# Modulo_Ignicao_Enertron_proto.net
KiCad netlist of a schematic drawn in EAGLE
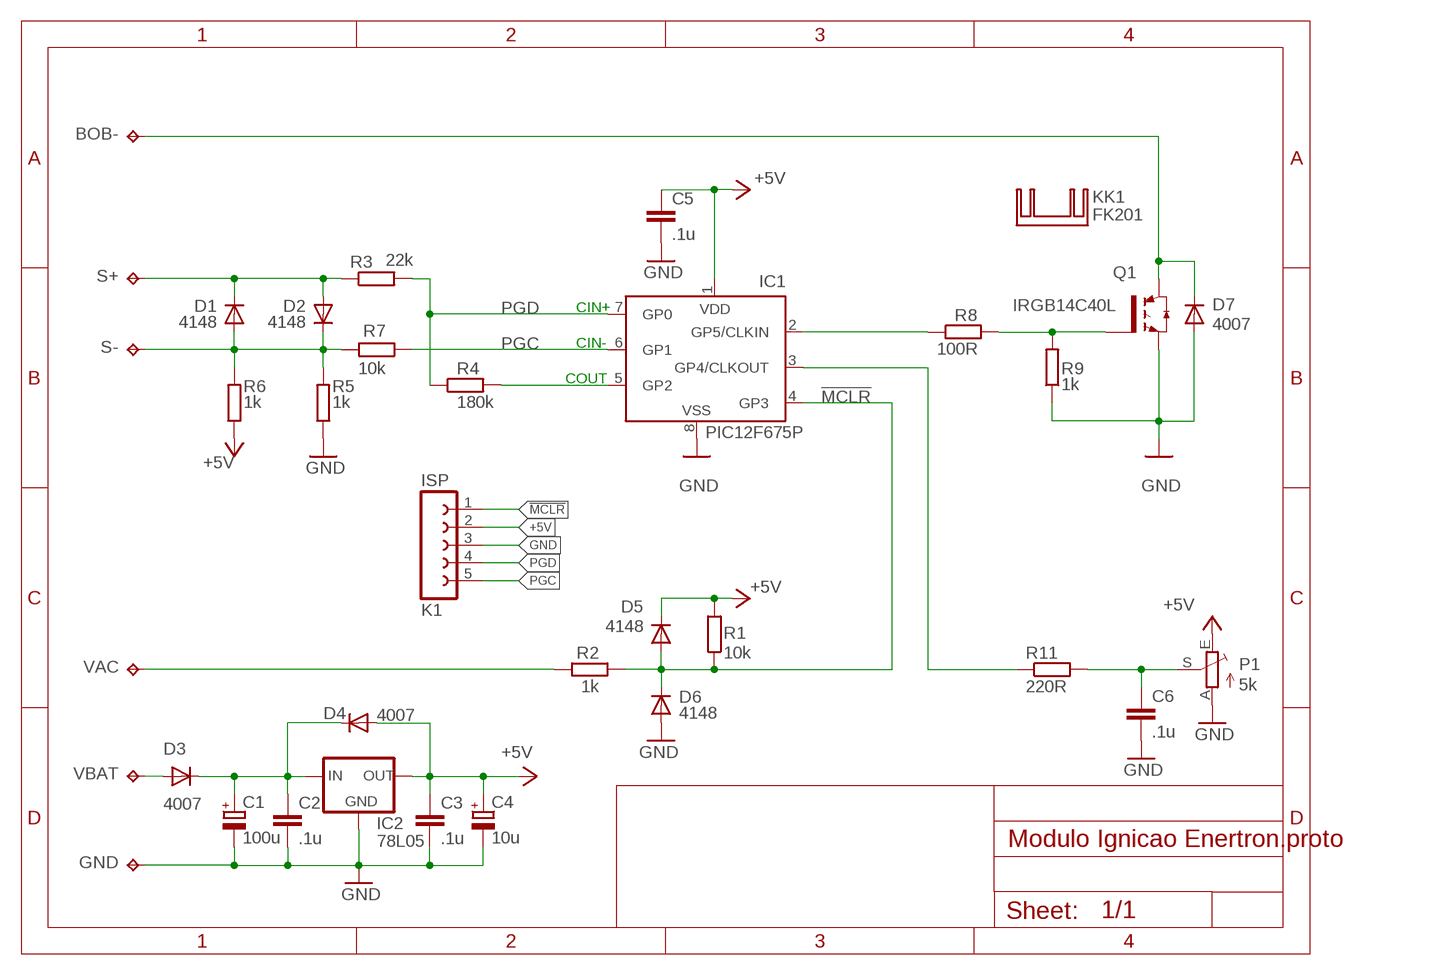
[diagram p0: schematic, sheet 1]

(export (version "E")
  (design (tool "Eeschema 10.0.6"))
  (components
    (comp (ref "BOB-")
      (value "TPPAD1-13Y")
      (footprint "eagle-import:P1-13Y")
      (libsource (lib "eagle-import") (part "TPPAD1-13Y"))
    )
    (comp (ref "C1")
      (value "100u")
      (footprint "eagle-import:E2,5-6")
      (libsource (lib "eagle-import") (part "CPOL-EUE2.5-6"))
    )
    (comp (ref "C2")
      (value ".1u")
      (footprint "eagle-import:C050-025X075L")
      (libsource (lib "eagle-import") (part "C-EUC050-025X075L"))
    )
    (comp (ref "C3")
      (value ".1u")
      (footprint "eagle-import:C050-025X075L")
      (libsource (lib "eagle-import") (part "C-EUC050-025X075L"))
    )
    (comp (ref "C4")
      (value "10u")
      (footprint "eagle-import:E2-4")
      (libsource (lib "eagle-import") (part "CPOL-EUE2-4"))
    )
    (comp (ref "C5")
      (value ".1u")
      (footprint "eagle-import:C050-025X075L")
      (libsource (lib "eagle-import") (part "C-EUC050-025X075L"))
    )
    (comp (ref "C6")
      (value ".1u")
      (footprint "eagle-import:C050-025X075L")
      (libsource (lib "eagle-import") (part "C-EUC050-025X075L"))
    )
    (comp (ref "D1")
      (value "4148")
      (footprint "eagle-import:D-5L")
      (libsource (lib "eagle-import") (part "DIODE-D-5L"))
    )
    (comp (ref "D2")
      (value "4148")
      (footprint "eagle-import:D-5L")
      (libsource (lib "eagle-import") (part "DIODE-D-5L"))
    )
    (comp (ref "D3")
      (value "4007")
      (footprint "eagle-import:D-7.5")
      (libsource (lib "eagle-import") (part "DIODE-D-7.5"))
    )
    (comp (ref "D4")
      (value "4007")
      (footprint "eagle-import:D-7.5")
      (libsource (lib "eagle-import") (part "DIODE-D-7.5"))
    )
    (comp (ref "D5")
      (value "4148")
      (footprint "eagle-import:D-5L")
      (libsource (lib "eagle-import") (part "DIODE-D-5L"))
    )
    (comp (ref "D6")
      (value "4148")
      (footprint "eagle-import:D-5L")
      (libsource (lib "eagle-import") (part "DIODE-D-5L"))
    )
    (comp (ref "D7")
      (value "4007")
      (footprint "eagle-import:DO07")
      (libsource (lib "eagle-import") (part "DIODE-DO07"))
    )
    (comp (ref "GND")
      (value "TPPAD1-13Y")
      (footprint "eagle-import:P1-13Y")
      (libsource (lib "eagle-import") (part "TPPAD1-13Y"))
    )
    (comp (ref "IC1")
      (value "PIC12F675P")
      (footprint "eagle-import:DIL8")
      (fields (field (name "MF") "MICROCHIP") (field (name "MPN") "PIC12F675-E/P"))
      (libsource (lib "eagle-import") (part "PIC12F6P75"))
    )
    (comp (ref "IC2")
      (value "78L05")
      (footprint "eagle-import:TO92-")
      (libsource (lib "eagle-import") (part "78LXX-"))
    )
    (comp (ref "K1")
      (value "ISP")
      (footprint "eagle-import:FE05-1")
      (libsource (lib "eagle-import") (part "FE05-1"))
    )
    (comp (ref "KK1")
      (value "FK201")
      (footprint "eagle-import:FK201")
      (libsource (lib "eagle-import") (part "FK201"))
    )
    (comp (ref "P1")
      (value "5k")
      (footprint "eagle-import:CA6V")
      (libsource (lib "eagle-import") (part "TRIM_EU-CA6V"))
    )
    (comp (ref "Q1")
      (value "IRGB14C40L")
      (footprint "eagle-import:TO262-V")
      (libsource (lib "eagle-import") (part "IRG4BC15UD--L"))
    )
    (comp (ref "R1")
      (value "10k")
      (footprint "eagle-import:0207_7L")
      (libsource (lib "eagle-import") (part "R-EU_0207/7L"))
    )
    (comp (ref "R2")
      (value "1k")
      (footprint "eagle-import:0207_7L")
      (libsource (lib "eagle-import") (part "R-EU_0207/7L"))
    )
    (comp (ref "R3")
      (value "22k")
      (footprint "eagle-import:0207_7L")
      (libsource (lib "eagle-import") (part "R-EU_0207/7L"))
    )
    (comp (ref "R4")
      (value "180k")
      (footprint "eagle-import:0207_7L")
      (libsource (lib "eagle-import") (part "R-EU_0207/7L"))
    )
    (comp (ref "R5")
      (value "1k")
      (footprint "eagle-import:0207_7L")
      (libsource (lib "eagle-import") (part "R-EU_0207/7L"))
    )
    (comp (ref "R6")
      (value "1k")
      (footprint "eagle-import:0207_7L")
      (libsource (lib "eagle-import") (part "R-EU_0207/7L"))
    )
    (comp (ref "R7")
      (value "10k")
      (footprint "eagle-import:0207_7L")
      (libsource (lib "eagle-import") (part "R-EU_0207/7L"))
    )
    (comp (ref "R8")
      (value "100R")
      (footprint "eagle-import:0207_7L")
      (libsource (lib "eagle-import") (part "R-EU_0207/7L"))
    )
    (comp (ref "R9")
      (value "1k")
      (footprint "eagle-import:0207_7L")
      (libsource (lib "eagle-import") (part "R-EU_0207/7L"))
    )
    (comp (ref "R11")
      (value "220R")
      (footprint "eagle-import:0207_7L")
      (libsource (lib "eagle-import") (part "R-EU_0207/7L"))
    )
    (comp (ref "S+")
      (value "TPPAD1-13Y")
      (footprint "eagle-import:P1-13Y")
      (libsource (lib "eagle-import") (part "TPPAD1-13Y"))
    )
    (comp (ref "S-")
      (value "TPPAD1-13Y")
      (footprint "eagle-import:P1-13Y")
      (libsource (lib "eagle-import") (part "TPPAD1-13Y"))
    )
    (comp (ref "VAC")
      (value "TPPAD1-13Y")
      (footprint "eagle-import:P1-13Y")
      (libsource (lib "eagle-import") (part "TPPAD1-13Y"))
    )
    (comp (ref "VBAT")
      (value "TPPAD1-13Y")
      (footprint "eagle-import:P1-13Y")
      (libsource (lib "eagle-import") (part "TPPAD1-13Y"))
    )
  )
  (nets
    (net (code "1") (name "+5V") (class "Default")
      (node (ref "C3") (pin "1") (pinfunction "1_1") (pintype "passive"))
      (node (ref "C4") (pin "+") (pinfunction "+_+") (pintype "passive"))
      (node (ref "C5") (pin "1") (pinfunction "1_1") (pintype "passive"))
      (node (ref "D4") (pin "A") (pinfunction "A_A") (pintype "passive"))
      (node (ref "D5") (pin "C") (pinfunction "C_C") (pintype "passive"))
      (node (ref "IC1") (pin "1") (pinfunction "VDD_1") (pintype "power_in"))
      (node (ref "IC2") (pin "3") (pinfunction "OUT_3") (pintype "passive"))
      (node (ref "K1") (pin "2") (pinfunction "2_2") (pintype "passive"))
      (node (ref "P1") (pin "E") (pinfunction "E_E") (pintype "passive"))
      (node (ref "R1") (pin "4") (pinfunction "2_4") (pintype "passive"))
      (node (ref "R6") (pin "3") (pinfunction "1_3") (pintype "passive"))
    )
    (net (code "2") (name "/~{MCLR}") (class "Default")
      (node (ref "D5") (pin "A") (pinfunction "A_A") (pintype "passive"))
      (node (ref "D6") (pin "C") (pinfunction "C_C") (pintype "passive"))
      (node (ref "IC1") (pin "4") (pinfunction "GP3_4") (pintype "input"))
      (node (ref "K1") (pin "1") (pinfunction "1_1") (pintype "passive"))
      (node (ref "R1") (pin "3") (pinfunction "1_3") (pintype "passive"))
      (node (ref "R2") (pin "3") (pinfunction "1_3") (pintype "passive"))
    )
    (net (code "3") (name "GND") (class "Default")
      (node (ref "C1") (pin "-") (pinfunction "-_-") (pintype "passive"))
      (node (ref "C2") (pin "2") (pinfunction "2_2") (pintype "passive"))
      (node (ref "C3") (pin "2") (pinfunction "2_2") (pintype "passive"))
      (node (ref "C4") (pin "-") (pinfunction "-_-") (pintype "passive"))
      (node (ref "C5") (pin "2") (pinfunction "2_2") (pintype "passive"))
      (node (ref "C6") (pin "2") (pinfunction "2_2") (pintype "passive"))
      (node (ref "D6") (pin "A") (pinfunction "A_A") (pintype "passive"))
      (node (ref "D7") (pin "A") (pinfunction "A_A") (pintype "passive"))
      (node (ref "GND") (pin "TP") (pinfunction "TP_TP") (pintype "input"))
      (node (ref "IC1") (pin "8") (pinfunction "VSS_8") (pintype "power_in"))
      (node (ref "IC2") (pin "2") (pinfunction "GND_2") (pintype "input"))
      (node (ref "K1") (pin "3") (pinfunction "3_3") (pintype "passive"))
      (node (ref "P1") (pin "A") (pinfunction "A_A") (pintype "passive"))
      (node (ref "Q1") (pin "3") (pinfunction "E_3") (pintype "passive"))
      (node (ref "R5") (pin "3") (pinfunction "1_3") (pintype "passive"))
      (node (ref "R9") (pin "3") (pinfunction "1_3") (pintype "passive"))
    )
    (net (code "4") (name "Net-(D3-PadA)") (class "Default")
      (node (ref "D3") (pin "A") (pinfunction "A_A") (pintype "passive"))
      (node (ref "VBAT") (pin "TP") (pinfunction "TP_TP") (pintype "input"))
    )
    (net (code "5") (name "Net-(IC1-GP2)") (class "Default")
      (node (ref "IC1") (pin "5") (pinfunction "GP2_5") (pintype "bidirectional"))
      (node (ref "R4") (pin "4") (pinfunction "2_4") (pintype "passive"))
    )
    (net (code "6") (name "Net-(IC1-GP4{slash}CLKOUT)") (class "Default")
      (node (ref "IC1") (pin "3") (pinfunction "GP4/CLKOUT_3") (pintype "bidirectional"))
      (node (ref "R11") (pin "3") (pinfunction "1_3") (pintype "passive"))
    )
    (net (code "7") (name "Net-(IC1-GP5{slash}CLKIN)") (class "Default")
      (node (ref "IC1") (pin "2") (pinfunction "GP5/CLKIN_2") (pintype "bidirectional"))
      (node (ref "R8") (pin "3") (pinfunction "1_3") (pintype "passive"))
    )
    (net (code "8") (name "Net-(IC2-IN)") (class "Default")
      (node (ref "C1") (pin "+") (pinfunction "+_+") (pintype "passive"))
      (node (ref "C2") (pin "1") (pinfunction "1_1") (pintype "passive"))
      (node (ref "D3") (pin "C") (pinfunction "C_C") (pintype "passive"))
      (node (ref "D4") (pin "C") (pinfunction "C_C") (pintype "passive"))
      (node (ref "IC2") (pin "1") (pinfunction "IN_1") (pintype "input"))
    )
    (net (code "9") (name "Net-(Q1-C)") (class "Default")
      (node (ref "BOB-") (pin "TP") (pinfunction "TP_TP") (pintype "input"))
      (node (ref "D7") (pin "C") (pinfunction "C_C") (pintype "passive"))
      (node (ref "Q1") (pin "2") (pinfunction "C_2") (pintype "passive"))
    )
    (net (code "10") (name "Net-(Q1-G)") (class "Default")
      (node (ref "Q1") (pin "1") (pinfunction "G_1") (pintype "passive"))
      (node (ref "R8") (pin "4") (pinfunction "2_4") (pintype "passive"))
      (node (ref "R9") (pin "4") (pinfunction "2_4") (pintype "passive"))
    )
    (net (code "11") (name "Net-(R2-2)") (class "Default")
      (node (ref "R2") (pin "4") (pinfunction "2_4") (pintype "passive"))
      (node (ref "VAC") (pin "TP") (pinfunction "TP_TP") (pintype "input"))
    )
    (net (code "12") (name "Net-(R3-1)") (class "Default")
      (node (ref "D1") (pin "C") (pinfunction "C_C") (pintype "passive"))
      (node (ref "D2") (pin "A") (pinfunction "A_A") (pintype "passive"))
      (node (ref "R3") (pin "3") (pinfunction "1_3") (pintype "passive"))
      (node (ref "S+") (pin "TP") (pinfunction "TP_TP") (pintype "input"))
    )
    (net (code "13") (name "Net-(R5-2)") (class "Default")
      (node (ref "D1") (pin "A") (pinfunction "A_A") (pintype "passive"))
      (node (ref "D2") (pin "C") (pinfunction "C_C") (pintype "passive"))
      (node (ref "R5") (pin "4") (pinfunction "2_4") (pintype "passive"))
      (node (ref "R6") (pin "4") (pinfunction "2_4") (pintype "passive"))
      (node (ref "R7") (pin "4") (pinfunction "2_4") (pintype "passive"))
      (node (ref "S-") (pin "TP") (pinfunction "TP_TP") (pintype "input"))
    )
    (net (code "14") (name "Net-(R11-2)") (class "Default")
      (node (ref "C6") (pin "1") (pinfunction "1_1") (pintype "passive"))
      (node (ref "P1") (pin "S") (pinfunction "S_S") (pintype "passive"))
      (node (ref "R11") (pin "4") (pinfunction "2_4") (pintype "passive"))
    )
    (net (code "15") (name "PGC") (class "Default")
      (node (ref "IC1") (pin "6") (pinfunction "GP1_6") (pintype "bidirectional"))
      (node (ref "K1") (pin "5") (pinfunction "5_5") (pintype "passive"))
      (node (ref "R7") (pin "3") (pinfunction "1_3") (pintype "passive"))
    )
    (net (code "16") (name "PGD") (class "Default")
      (node (ref "IC1") (pin "7") (pinfunction "GP0_7") (pintype "bidirectional"))
      (node (ref "K1") (pin "4") (pinfunction "4_4") (pintype "passive"))
      (node (ref "R3") (pin "4") (pinfunction "2_4") (pintype "passive"))
      (node (ref "R4") (pin "3") (pinfunction "1_3") (pintype "passive"))
    )
  )
)
